# design.net
KiCad netlist of a schematic drawn in EasyEDA Pro
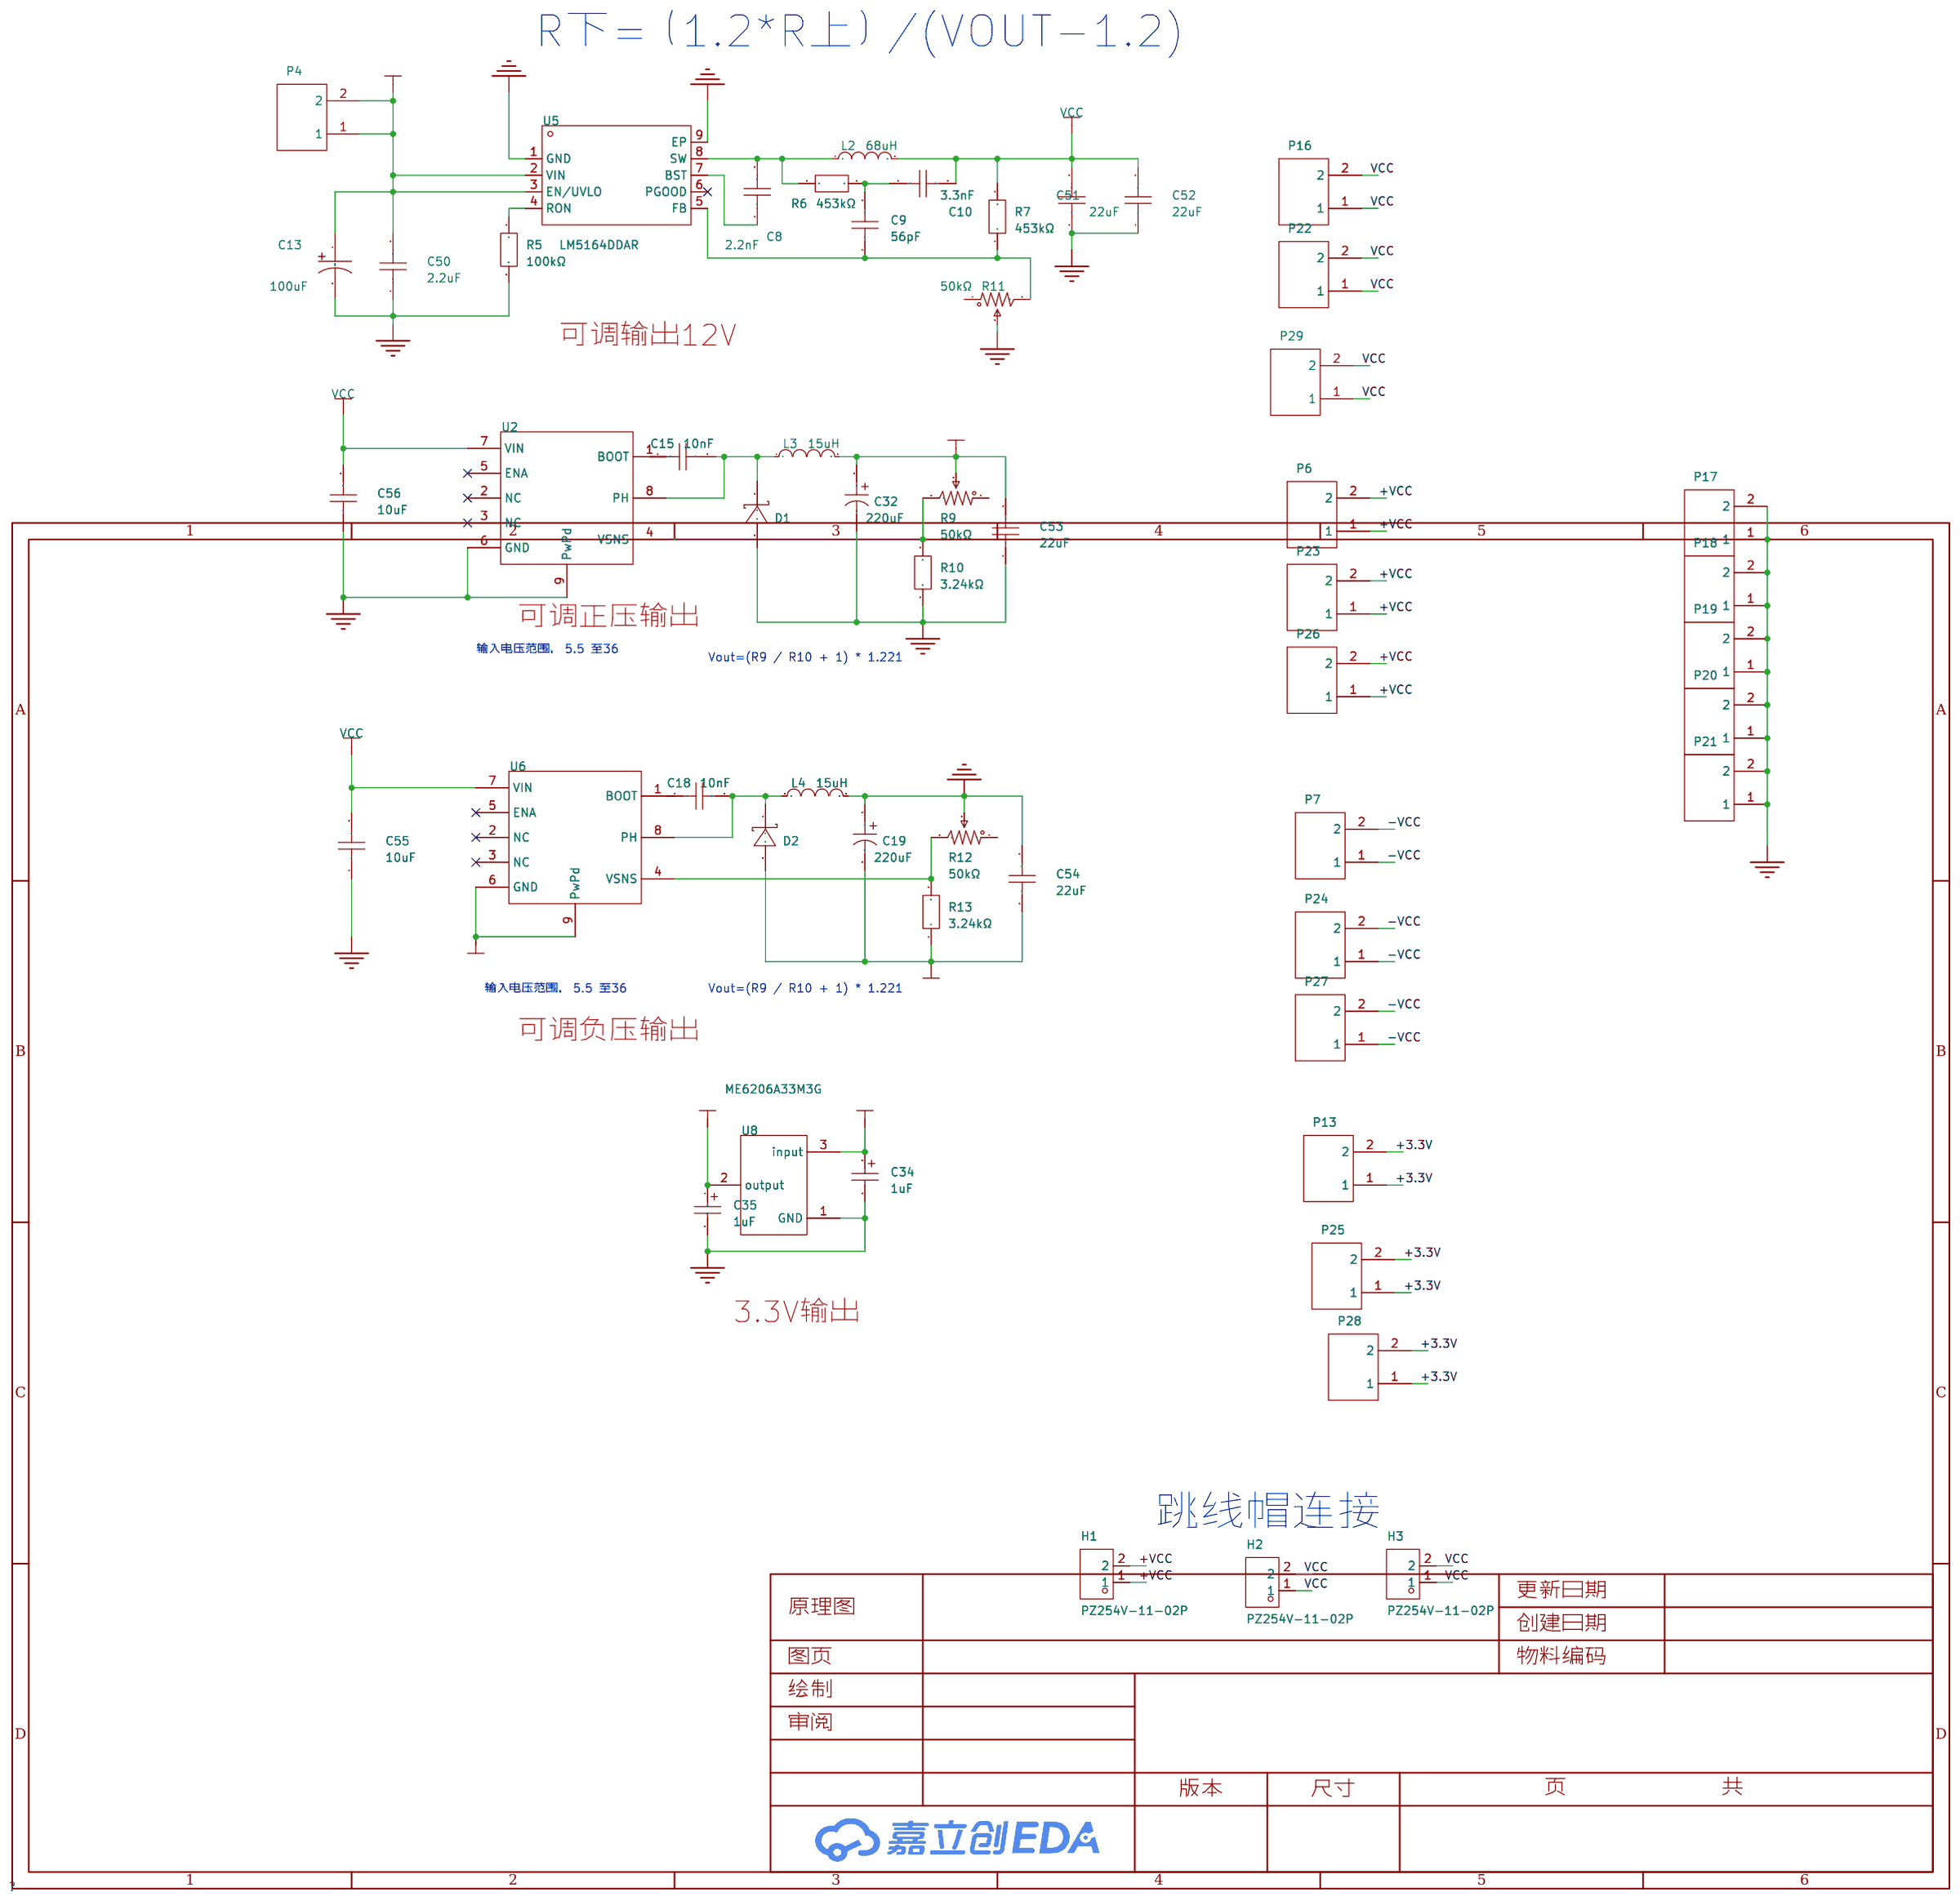
[diagram p0: schematic sheet]

(export (version "E")
  (design (tool "Eeschema 10.0.6"))
  (components
    (comp (ref "C8")
      (value "2.2nF")
      (footprint "easyedapro:C0805")
      (description "容值:2.2nF;精度:±5%;额定电压:250V;材质(温度系数):C0G;")
      (fields
        (field (name "Manufacturer Part") "C0805X222JAGACAUTO")
        (field (name "Manufacturer") "KEMET(基美)")
      )
      (libsource (lib "easyedapro") (part "C0805X222JAGACAUTO"))
    )
    (comp (ref "C9")
      (value "56pF")
      (footprint "easyedapro:C0805")
      (description "容值:56pF;精度:±5%;额定电压:250V;材质(温度系数):C0G;")
      (fields
        (field (name "Manufacturer Part") "GRM21A5C2E560JW01D")
        (field (name "Manufacturer") "muRata(村田)")
      )
      (libsource (lib "easyedapro") (part "GRM21A5C2E560JW01D"))
    )
    (comp (ref "C10")
      (value "3.3nF")
      (footprint "easyedapro:C0805")
      (description "容值:3.3nF;精度:±10%;额定电压:50V;材质(温度系数):X7R;")
      (fields
        (field (name "Manufacturer Part") "GRM216R71H332KA01D")
        (field (name "Manufacturer") "muRata(村田)")
      )
      (libsource (lib "easyedapro") (part "GRM216R71H332KA01D"))
    )
    (comp (ref "C13")
      (value "100uF")
      (footprint "easyedapro:CAP-TH_BD10.0-P5.00-D1.0-FD")
      (fields
        (field (name "Manufacturer Part") "RC100M101LO10*16TH-2A1E")
        (field (name "Manufacturer") "BERYL(绿宝石)")
      )
      (libsource (lib "easyedapro") (part "RC100M101LO10*16TH-2A1E"))
    )
    (comp (ref "C15")
      (value "10nF")
      (footprint "easyedapro:C0805")
      (description "容值:10nF;精度:±10%;额定电压:50V;材质(温度系数):X8R;")
      (fields (field (name "Manufacturer Part") "C0805C103K5HACTU") (field (name "Manufacturer") "KEMET(基美)"))
      (libsource (lib "easyedapro") (part "C0805C103K5HACTU"))
    )
    (comp (ref "C18")
      (value "10nF")
      (footprint "easyedapro:C0805")
      (description "容值:10nF;精度:±10%;额定电压:50V;材质(温度系数):X8R;")
      (fields (field (name "Manufacturer Part") "C0805C103K5HACTU") (field (name "Manufacturer") "KEMET(基美)"))
      (libsource (lib "easyedapro") (part "C0805C103K5HACTU"))
    )
    (comp (ref "C19")
      (value "220uF")
      (fields (field (name "Manufacturer Part") "ERE1VM221F12OT") (field (name "Manufacturer") "AISHI(艾华集团)"))
      (libsource (lib "easyedapro") (part "RVE100UF35V67RV0072"))
    )
    (comp (ref "C32")
      (value "220uF")
      (fields (field (name "Manufacturer Part") "ERE1VM221F12OT") (field (name "Manufacturer") "AISHI(艾华集团)"))
      (libsource (lib "easyedapro") (part "RVE100UF35V67RV0072"))
    )
    (comp (ref "C34")
      (value "1uF")
      (footprint "easyedapro:CASE-A_3216")
      (description "容值:1uF;精度:±10%;额定电压:35V;等效串联电阻:7.5Ω@100kHz;")
      (fields (field (name "Manufacturer Part") "TAJA105K035RNJ") (field (name "Manufacturer") "Kyocera AVX"))
      (libsource (lib "easyedapro") (part "TAJA105K035RNJ"))
    )
    (comp (ref "C35")
      (value "1uF")
      (footprint "easyedapro:CASE-A_3216")
      (description "容值:1uF;精度:±10%;额定电压:35V;等效串联电阻:7.5Ω@100kHz;")
      (fields (field (name "Manufacturer Part") "TAJA105K035RNJ") (field (name "Manufacturer") "Kyocera AVX"))
      (libsource (lib "easyedapro") (part "TAJA105K035RNJ"))
    )
    (comp (ref "C50")
      (value "2.2uF")
      (footprint "easyedapro:C0805")
      (description "容值:2.2uF;精度:±10%;额定电压:100V;材质(温度系数):X7R;")
      (fields
        (field (name "Manufacturer Part") "CGA0805X7R225K101MT")
        (field (name "Manufacturer") "HRE(芯声)")
      )
      (libsource (lib "easyedapro") (part "CGA0805X7R225K101MT"))
    )
    (comp (ref "C51")
      (value "22uF")
      (footprint "easyedapro:C0805")
      (description "容值:22uF;精度:±20%;额定电压:35V;材质(温度系数):X5R;")
      (fields
        (field (name "Manufacturer Part") "CGA0805X5R226M350MT")
        (field (name "Manufacturer") "HRE(芯声)")
      )
      (libsource (lib "easyedapro") (part "CGA0805X5R226M350MT"))
    )
    (comp (ref "C52")
      (value "22uF")
      (footprint "easyedapro:C0805")
      (description "容值:22uF;精度:±20%;额定电压:35V;材质(温度系数):X5R;")
      (fields
        (field (name "Manufacturer Part") "CGA0805X5R226M350MT")
        (field (name "Manufacturer") "HRE(芯声)")
      )
      (libsource (lib "easyedapro") (part "CGA0805X5R226M350MT"))
    )
    (comp (ref "C53")
      (value "22uF")
      (footprint "easyedapro:C0805")
      (description "容值:22uF;精度:±20%;额定电压:35V;材质(温度系数):X5R;")
      (fields
        (field (name "Manufacturer Part") "CGA0805X5R226M350MT")
        (field (name "Manufacturer") "HRE(芯声)")
      )
      (libsource (lib "easyedapro") (part "CGA0805X5R226M350MT"))
    )
    (comp (ref "C54")
      (value "22uF")
      (footprint "easyedapro:C0805")
      (description "容值:22uF;精度:±20%;额定电压:35V;材质(温度系数):X5R;")
      (fields
        (field (name "Manufacturer Part") "CGA0805X5R226M350MT")
        (field (name "Manufacturer") "HRE(芯声)")
      )
      (libsource (lib "easyedapro") (part "CGA0805X5R226M350MT"))
    )
    (comp (ref "C55")
      (value "10uF")
      (footprint "easyedapro:C0805")
      (description "容值:10uF;精度:±10%;额定电压:50V;材质(温度系数):X5R;")
      (fields
        (field (name "Manufacturer Part") "GRM21BR61H106KE43L")
        (field (name "Manufacturer") "muRata(村田)")
      )
      (libsource (lib "easyedapro") (part "GRM21BR61H106KE43L"))
    )
    (comp (ref "C56")
      (value "10uF")
      (footprint "easyedapro:C0805")
      (description "容值:10uF;精度:±10%;额定电压:50V;材质(温度系数):X5R;")
      (fields
        (field (name "Manufacturer Part") "GRM21BR61H106KE43L")
        (field (name "Manufacturer") "muRata(村田)")
      )
      (libsource (lib "easyedapro") (part "GRM21BR61H106KE43L"))
    )
    (comp (ref "D1")
      (value "B340A")
      (footprint "easyedapro:SMA_L4.3-W2.6-LS5.1-RD")
      (description "直流反向耐压(Vr):40V;平均整流电流(Io):3A;正向压降(Vf):550mV@3A;")
      (fields (field (name "Manufacturer") "MDD"))
      (libsource (lib "easyedapro") (part "B340A"))
    )
    (comp (ref "D2")
      (value "B340A")
      (footprint "easyedapro:SMA_L4.3-W2.6-LS5.1-RD")
      (description "直流反向耐压(Vr):40V;平均整流电流(Io):3A;正向压降(Vf):550mV@3A;")
      (fields (field (name "Manufacturer") "MDD"))
      (libsource (lib "easyedapro") (part "B340A"))
    )
    (comp (ref "H1")
      (value "PZ254V-11-02P")
      (footprint "easyedapro:HDR-TH_2P-P2.54-V-M")
      (fields (field (name "Manufacturer") "XFCN(兴飞)"))
      (libsource (lib "easyedapro") (part "PZ254V-11-02P"))
    )
    (comp (ref "H2")
      (value "PZ254V-11-02P")
      (footprint "easyedapro:HDR-TH_2P-P2.54-V-M")
      (fields (field (name "Manufacturer") "XFCN(兴飞)"))
      (libsource (lib "easyedapro") (part "PZ254V-11-02P"))
    )
    (comp (ref "H3")
      (value "PZ254V-11-02P")
      (footprint "easyedapro:HDR-TH_2P-P2.54-V-M")
      (fields (field (name "Manufacturer") "XFCN(兴飞)"))
      (libsource (lib "easyedapro") (part "PZ254V-11-02P"))
    )
    (comp (ref "L2")
      (value "68uH")
      (footprint "easyedapro:IND-SMD_L13.5-W12.8_APH1265T")
      (description "电感值:68uH;精度:±20%;额定电流:4.1A;饱和电流(Isat):4.3A;类型:一体成型电感;")
      (fields (field (name "Manufacturer Part") "APH1265T680M") (field (name "Manufacturer") "APV(爱普微)"))
      (libsource (lib "easyedapro") (part "APH1265T680M"))
    )
    (comp (ref "L3")
      (value "15uH")
      (footprint "easyedapro:IND-SMD_L7.3-W6.8")
      (description "精度:±20%;额定电流:3A;电感值:15uH;直流电阻(DCR):113mΩ;")
      (fields
        (field (name "Manufacturer Part") "MWSA0603S-150MT")
        (field (name "Manufacturer") "Sunlord(顺络)")
      )
      (libsource (lib "easyedapro") (part "MWSA0603S-150MT"))
    )
    (comp (ref "L4")
      (value "15uH")
      (footprint "easyedapro:IND-SMD_L7.3-W6.8")
      (description "精度:±20%;额定电流:3A;电感值:15uH;直流电阻(DCR):113mΩ;")
      (fields
        (field (name "Manufacturer Part") "MWSA0603S-150MT")
        (field (name "Manufacturer") "Sunlord(顺络)")
      )
      (libsource (lib "easyedapro") (part "MWSA0603S-150MT"))
    )
    (comp (ref "P4")
      (value "WJ128V-5.0-2P")
      (footprint "easyedapro:CONN-TH_2P-P5.00_WJ128V-5.0-2P")
      (fields (field (name "Manufacturer") "KANGNEX(康奈克斯电气)"))
      (libsource (lib "easyedapro") (part "WJ128V-5.0-2P"))
    )
    (comp (ref "P6")
      (value "WJ128V-5.0-2P")
      (footprint "easyedapro:CONN-TH_2P-P5.00_WJ128V-5.0-2P")
      (fields (field (name "Manufacturer") "KANGNEX(康奈克斯电气)"))
      (libsource (lib "easyedapro") (part "WJ128V-5.0-2P"))
    )
    (comp (ref "P7")
      (value "WJ128V-5.0-2P")
      (footprint "easyedapro:CONN-TH_2P-P5.00_WJ128V-5.0-2P")
      (fields (field (name "Manufacturer") "KANGNEX(康奈克斯电气)"))
      (libsource (lib "easyedapro") (part "WJ128V-5.0-2P"))
    )
    (comp (ref "P13")
      (value "WJ128V-5.0-2P")
      (footprint "easyedapro:CONN-TH_2P-P5.00_WJ128V-5.0-2P")
      (fields (field (name "Manufacturer") "KANGNEX(康奈克斯电气)"))
      (libsource (lib "easyedapro") (part "WJ128V-5.0-2P"))
    )
    (comp (ref "P16")
      (value "WJ128V-5.0-2P")
      (footprint "easyedapro:CONN-TH_2P-P5.00_WJ128V-5.0-2P")
      (fields (field (name "Manufacturer") "KANGNEX(康奈克斯电气)"))
      (libsource (lib "easyedapro") (part "WJ128V-5.0-2P"))
    )
    (comp (ref "P17")
      (value "WJ128V-5.0-2P")
      (footprint "easyedapro:CONN-TH_2P-P5.00_WJ128V-5.0-2P")
      (fields (field (name "Manufacturer") "KANGNEX(康奈克斯电气)"))
      (libsource (lib "easyedapro") (part "WJ128V-5.0-2P"))
    )
    (comp (ref "P18")
      (value "WJ128V-5.0-2P")
      (footprint "easyedapro:CONN-TH_2P-P5.00_WJ128V-5.0-2P")
      (fields (field (name "Manufacturer") "KANGNEX(康奈克斯电气)"))
      (libsource (lib "easyedapro") (part "WJ128V-5.0-2P"))
    )
    (comp (ref "P19")
      (value "WJ128V-5.0-2P")
      (footprint "easyedapro:CONN-TH_2P-P5.00_WJ128V-5.0-2P")
      (fields (field (name "Manufacturer") "KANGNEX(康奈克斯电气)"))
      (libsource (lib "easyedapro") (part "WJ128V-5.0-2P"))
    )
    (comp (ref "P20")
      (value "WJ128V-5.0-2P")
      (footprint "easyedapro:CONN-TH_2P-P5.00_WJ128V-5.0-2P")
      (fields (field (name "Manufacturer") "KANGNEX(康奈克斯电气)"))
      (libsource (lib "easyedapro") (part "WJ128V-5.0-2P"))
    )
    (comp (ref "P21")
      (value "WJ128V-5.0-2P")
      (footprint "easyedapro:CONN-TH_2P-P5.00_WJ128V-5.0-2P")
      (fields (field (name "Manufacturer") "KANGNEX(康奈克斯电气)"))
      (libsource (lib "easyedapro") (part "WJ128V-5.0-2P"))
    )
    (comp (ref "P22")
      (value "WJ128V-5.0-2P")
      (footprint "easyedapro:CONN-TH_2P-P5.00_WJ128V-5.0-2P")
      (fields (field (name "Manufacturer") "KANGNEX(康奈克斯电气)"))
      (libsource (lib "easyedapro") (part "WJ128V-5.0-2P"))
    )
    (comp (ref "P23")
      (value "WJ128V-5.0-2P")
      (footprint "easyedapro:CONN-TH_2P-P5.00_WJ128V-5.0-2P")
      (fields (field (name "Manufacturer") "KANGNEX(康奈克斯电气)"))
      (libsource (lib "easyedapro") (part "WJ128V-5.0-2P"))
    )
    (comp (ref "P24")
      (value "WJ128V-5.0-2P")
      (footprint "easyedapro:CONN-TH_2P-P5.00_WJ128V-5.0-2P")
      (fields (field (name "Manufacturer") "KANGNEX(康奈克斯电气)"))
      (libsource (lib "easyedapro") (part "WJ128V-5.0-2P"))
    )
    (comp (ref "P25")
      (value "WJ128V-5.0-2P")
      (footprint "easyedapro:CONN-TH_2P-P5.00_WJ128V-5.0-2P")
      (fields (field (name "Manufacturer") "KANGNEX(康奈克斯电气)"))
      (libsource (lib "easyedapro") (part "WJ128V-5.0-2P"))
    )
    (comp (ref "P26")
      (value "WJ128V-5.0-2P")
      (footprint "easyedapro:CONN-TH_2P-P5.00_WJ128V-5.0-2P")
      (fields (field (name "Manufacturer") "KANGNEX(康奈克斯电气)"))
      (libsource (lib "easyedapro") (part "WJ128V-5.0-2P"))
    )
    (comp (ref "P27")
      (value "WJ128V-5.0-2P")
      (footprint "easyedapro:CONN-TH_2P-P5.00_WJ128V-5.0-2P")
      (fields (field (name "Manufacturer") "KANGNEX(康奈克斯电气)"))
      (libsource (lib "easyedapro") (part "WJ128V-5.0-2P"))
    )
    (comp (ref "P28")
      (value "WJ128V-5.0-2P")
      (footprint "easyedapro:CONN-TH_2P-P5.00_WJ128V-5.0-2P")
      (fields (field (name "Manufacturer") "KANGNEX(康奈克斯电气)"))
      (libsource (lib "easyedapro") (part "WJ128V-5.0-2P"))
    )
    (comp (ref "P29")
      (value "WJ128V-5.0-2P")
      (footprint "easyedapro:CONN-TH_2P-P5.00_WJ128V-5.0-2P")
      (fields (field (name "Manufacturer") "KANGNEX(康奈克斯电气)"))
      (libsource (lib "easyedapro") (part "WJ128V-5.0-2P"))
    )
    (comp (ref "R5")
      (value "100kΩ")
      (footprint "easyedapro:R0805")
      (description "电阻类型:薄膜电阻;阻值:100kΩ;精度:±0.01%;温度系数:±5ppm/°C;")
      (fields
        (field (name "Manufacturer Part") "TP0805T100KP0505Z")
        (field (name "Manufacturer") "EVER OHMS(天二科技)")
      )
      (libsource (lib "easyedapro") (part "TP0805T100KP0505Z"))
    )
    (comp (ref "R6")
      (value "453kΩ")
      (footprint "easyedapro:R0805")
      (description "电阻类型:薄膜电阻;阻值:100kΩ;精度:±0.01%;温度系数:±5ppm/°C;")
      (fields
        (field (name "Manufacturer Part") "TP0805T100KP0505Z")
        (field (name "Manufacturer") "EVER OHMS(天二科技)")
      )
      (libsource (lib "easyedapro") (part "TP0805T100KP0505Z"))
    )
    (comp (ref "R7")
      (value "453kΩ")
      (footprint "easyedapro:R0805")
      (description "电阻类型:薄膜电阻;阻值:453kΩ;精度:±0.5%;功率:100mW;最大工作电压:100V;温度系数:±25ppm/°C;")
      (fields (field (name "Manufacturer Part") "RR1220P-4533-D-M") (field (name "Manufacturer") "SUSUMU"))
      (libsource (lib "easyedapro") (part "RR1220P-4533-D-M"))
    )
    (comp (ref "R9")
      (value "50kΩ")
      (fields (field (name "Manufacturer Part") "3296W-1-503") (field (name "Manufacturer") "BOCHEN(博晨)"))
      (libsource (lib "easyedapro") (part "3296W-1-103"))
    )
    (comp (ref "R10")
      (value "3.24kΩ")
      (footprint "easyedapro:R0805")
      (description "阻值:3.24kΩ;精度:±1%;功率:125mW;")
      (fields (field (name "Manufacturer Part") "RCA053K24FLF") (field (name "Manufacturer") "HKR(香港电阻)"))
      (libsource (lib "easyedapro") (part "RCA053K24FLF"))
    )
    (comp (ref "R11")
      (value "50kΩ")
      (fields (field (name "Manufacturer Part") "3296W-1-503") (field (name "Manufacturer") "BOCHEN(博晨)"))
      (libsource (lib "easyedapro") (part "3296W-1-103"))
    )
    (comp (ref "R12")
      (value "50kΩ")
      (fields (field (name "Manufacturer Part") "3296W-1-503") (field (name "Manufacturer") "BOCHEN(博晨)"))
      (libsource (lib "easyedapro") (part "3296W-1-103"))
    )
    (comp (ref "R13")
      (value "3.24kΩ")
      (footprint "easyedapro:R0805")
      (description "阻值:3.24kΩ;精度:±1%;功率:125mW;")
      (fields (field (name "Manufacturer Part") "RCA053K24FLF") (field (name "Manufacturer") "HKR(香港电阻)"))
      (libsource (lib "easyedapro") (part "RCA053K24FLF"))
    )
    (comp (ref "U2")
      (value "TPS5430DDAR")
      (footprint "easyedapro:ESOP-8_L4.9-W3.9-P1.27-LS6.0-TL-EP")
      (description "功能类型:降压型;同步整流:-;输出通道数:-;拓扑结构:-;输入电压:-;输出电流(最大值):-;开关频率:-;")
      (fields (field (name "Manufacturer") "TI(德州仪器)"))
      (libsource (lib "easyedapro") (part "TPS5430DDAR"))
    )
    (comp (ref "U5")
      (value "LM5164DDAR")
      (footprint "easyedapro:SO-8_L4.9-W3.9-P1.27-LS6.0-BL-EP")
      (description "功能类型:降压型;输出类型:可调;输入电压:6V~100V;输出电压:1.2V~100V;输出电流(最大值):1A;")
      (fields (field (name "Manufacturer") "TI(德州仪器)"))
      (libsource (lib "easyedapro") (part "LM5164DDAR"))
    )
    (comp (ref "U6")
      (value "TPS5430DDAR")
      (footprint "easyedapro:ESOP-8_L4.9-W3.9-P1.27-LS6.0-TL-EP")
      (description "功能类型:降压型;同步整流:-;输出通道数:-;拓扑结构:-;输入电压:-;输出电流(最大值):-;开关频率:-;")
      (fields (field (name "Manufacturer") "TI(德州仪器)"))
      (libsource (lib "easyedapro") (part "TPS5430DDAR"))
    )
    (comp (ref "U8")
      (value "ME6206A33M3G")
      (footprint "easyedapro:SOT-23-3_L2.9-W1.6-P1.90-LS2.8-BR")
      (description "输出类型:固定;输出极性:正;最大输入电压:6V;输出电压:3.3V;输出电流:300mA;电源纹波抑制比(PSRR):50dB@(1kHz);")
      (fields (field (name "Manufacturer") "MICRONE(南京微盟)"))
      (libsource (lib "easyedapro") (part "ME6206A33M3G"))
    )
  )
  (nets
    (net (code "1") (name "+3.3V") (class "Default")
      (node (ref "C35") (pin "1") (pinfunction "1_1") (pintype "input"))
      (node (ref "P13") (pin "1") (pinfunction "1_1") (pintype "unspecified"))
      (node (ref "P13") (pin "2") (pinfunction "2_2") (pintype "unspecified"))
      (node (ref "P25") (pin "1") (pinfunction "1_1") (pintype "unspecified"))
      (node (ref "P25") (pin "2") (pinfunction "2_2") (pintype "unspecified"))
      (node (ref "P28") (pin "1") (pinfunction "1_1") (pintype "unspecified"))
      (node (ref "P28") (pin "2") (pinfunction "2_2") (pintype "unspecified"))
      (node (ref "U8") (pin "2") (pinfunction "output_2") (pintype "input"))
    )
    (net (code "2") (name "+VCC") (class "Default")
      (node (ref "C32") (pin "1") (pinfunction "1_1") (pintype "input"))
      (node (ref "C34") (pin "1") (pinfunction "1_1") (pintype "input"))
      (node (ref "C53") (pin "2") (pinfunction "2_2") (pintype "unspecified"))
      (node (ref "H1") (pin "1") (pinfunction "1_1") (pintype "unspecified"))
      (node (ref "H1") (pin "2") (pinfunction "2_2") (pintype "unspecified"))
      (node (ref "L3") (pin "2") (pinfunction "2_2") (pintype "input"))
      (node (ref "P23") (pin "1") (pinfunction "1_1") (pintype "unspecified"))
      (node (ref "P23") (pin "2") (pinfunction "2_2") (pintype "unspecified"))
      (node (ref "P26") (pin "1") (pinfunction "1_1") (pintype "unspecified"))
      (node (ref "P26") (pin "2") (pinfunction "2_2") (pintype "unspecified"))
      (node (ref "P6") (pin "1") (pinfunction "1_1") (pintype "unspecified"))
      (node (ref "P6") (pin "2") (pinfunction "2_2") (pintype "unspecified"))
      (node (ref "R9") (pin "2") (pinfunction "2_2") (pintype "input"))
      (node (ref "U8") (pin "3") (pinfunction "input_3") (pintype "input"))
    )
    (net (code "3") (name "-VCC") (class "Default")
      (node (ref "C19") (pin "2") (pinfunction "2_2") (pintype "input"))
      (node (ref "C54") (pin "1") (pinfunction "1_1") (pintype "unspecified"))
      (node (ref "D2") (pin "2") (pinfunction "A_2") (pintype "input"))
      (node (ref "P24") (pin "1") (pinfunction "1_1") (pintype "unspecified"))
      (node (ref "P24") (pin "2") (pinfunction "2_2") (pintype "unspecified"))
      (node (ref "P27") (pin "1") (pinfunction "1_1") (pintype "unspecified"))
      (node (ref "P27") (pin "2") (pinfunction "2_2") (pintype "unspecified"))
      (node (ref "P7") (pin "1") (pinfunction "1_1") (pintype "unspecified"))
      (node (ref "P7") (pin "2") (pinfunction "2_2") (pintype "unspecified"))
      (node (ref "R13") (pin "1") (pinfunction "1_1") (pintype "unspecified"))
      (node (ref "U6") (pin "6") (pinfunction "GND_6") (pintype "input"))
      (node (ref "U6") (pin "9") (pinfunction "PwPd_9") (pintype "input"))
    )
    (net (code "4") (name "GND") (class "Default")
      (node (ref "C13") (pin "2") (pinfunction "2_2") (pintype "input"))
      (node (ref "C19") (pin "1") (pinfunction "1_1") (pintype "input"))
      (node (ref "C32") (pin "2") (pinfunction "2_2") (pintype "input"))
      (node (ref "C34") (pin "2") (pinfunction "2_2") (pintype "input"))
      (node (ref "C35") (pin "2") (pinfunction "2_2") (pintype "input"))
      (node (ref "C50") (pin "1") (pinfunction "1_1") (pintype "unspecified"))
      (node (ref "C51") (pin "1") (pinfunction "1_1") (pintype "unspecified"))
      (node (ref "C52") (pin "1") (pinfunction "1_1") (pintype "unspecified"))
      (node (ref "C53") (pin "1") (pinfunction "1_1") (pintype "unspecified"))
      (node (ref "C54") (pin "2") (pinfunction "2_2") (pintype "unspecified"))
      (node (ref "C55") (pin "1") (pinfunction "1_1") (pintype "unspecified"))
      (node (ref "C56") (pin "1") (pinfunction "1_1") (pintype "unspecified"))
      (node (ref "D1") (pin "2") (pinfunction "A_2") (pintype "input"))
      (node (ref "L4") (pin "2") (pinfunction "2_2") (pintype "input"))
      (node (ref "P17") (pin "1") (pinfunction "1_1") (pintype "unspecified"))
      (node (ref "P17") (pin "2") (pinfunction "2_2") (pintype "unspecified"))
      (node (ref "P18") (pin "1") (pinfunction "1_1") (pintype "unspecified"))
      (node (ref "P18") (pin "2") (pinfunction "2_2") (pintype "unspecified"))
      (node (ref "P19") (pin "1") (pinfunction "1_1") (pintype "unspecified"))
      (node (ref "P19") (pin "2") (pinfunction "2_2") (pintype "unspecified"))
      (node (ref "P20") (pin "1") (pinfunction "1_1") (pintype "unspecified"))
      (node (ref "P20") (pin "2") (pinfunction "2_2") (pintype "unspecified"))
      (node (ref "P21") (pin "1") (pinfunction "1_1") (pintype "unspecified"))
      (node (ref "P21") (pin "2") (pinfunction "2_2") (pintype "unspecified"))
      (node (ref "R10") (pin "1") (pinfunction "1_1") (pintype "unspecified"))
      (node (ref "R11") (pin "2") (pinfunction "2_2") (pintype "input"))
      (node (ref "R12") (pin "2") (pinfunction "2_2") (pintype "input"))
      (node (ref "R5") (pin "2") (pinfunction "2_2") (pintype "unspecified"))
      (node (ref "U2") (pin "6") (pinfunction "GND_6") (pintype "input"))
      (node (ref "U2") (pin "9") (pinfunction "PwPd_9") (pintype "input"))
      (node (ref "U5") (pin "1") (pinfunction "GND_1") (pintype "input"))
      (node (ref "U5") (pin "9") (pinfunction "EP_9") (pintype "input"))
      (node (ref "U8") (pin "1") (pinfunction "GND_1") (pintype "input"))
    )
    (net (code "5") (name "Net-(C10-Pad1)") (class "Default")
      (node (ref "C10") (pin "1") (pinfunction "1_1") (pintype "unspecified"))
      (node (ref "C9") (pin "2") (pinfunction "2_2") (pintype "unspecified"))
      (node (ref "R6") (pin "1") (pinfunction "1_1") (pintype "unspecified"))
    )
    (net (code "6") (name "Net-(D1-K)") (class "Default")
      (node (ref "C15") (pin "2") (pinfunction "2_2") (pintype "unspecified"))
      (node (ref "D1") (pin "1") (pinfunction "K_1") (pintype "input"))
      (node (ref "L3") (pin "1") (pinfunction "1_1") (pintype "input"))
      (node (ref "U2") (pin "8") (pinfunction "PH_8") (pintype "input"))
    )
    (net (code "7") (name "Net-(D2-K)") (class "Default")
      (node (ref "C18") (pin "2") (pinfunction "2_2") (pintype "unspecified"))
      (node (ref "D2") (pin "1") (pinfunction "K_1") (pintype "input"))
      (node (ref "L4") (pin "1") (pinfunction "1_1") (pintype "input"))
      (node (ref "U6") (pin "8") (pinfunction "PH_8") (pintype "input"))
    )
    (net (code "8") (name "Net-(U2-BOOT)") (class "Default")
      (node (ref "C15") (pin "1") (pinfunction "1_1") (pintype "unspecified"))
      (node (ref "U2") (pin "1") (pinfunction "BOOT_1") (pintype "input"))
    )
    (net (code "9") (name "Net-(U2-VSNS)") (class "Default")
      (node (ref "R10") (pin "2") (pinfunction "2_2") (pintype "unspecified"))
      (node (ref "R9") (pin "3") (pinfunction "3_3") (pintype "input"))
      (node (ref "U2") (pin "4") (pinfunction "VSNS_4") (pintype "input"))
    )
    (net (code "10") (name "Net-(U5-BST)") (class "Default")
      (node (ref "C8") (pin "1") (pinfunction "1_1") (pintype "unspecified"))
      (node (ref "U5") (pin "7") (pinfunction "BST_7") (pintype "input"))
    )
    (net (code "11") (name "Net-(U5-FB)") (class "Default")
      (node (ref "C9") (pin "1") (pinfunction "1_1") (pintype "unspecified"))
      (node (ref "R11") (pin "3") (pinfunction "3_3") (pintype "input"))
      (node (ref "R7") (pin "1") (pinfunction "1_1") (pintype "unspecified"))
      (node (ref "U5") (pin "5") (pinfunction "FB_5") (pintype "input"))
    )
    (net (code "12") (name "Net-(U5-RON)") (class "Default")
      (node (ref "R5") (pin "1") (pinfunction "1_1") (pintype "unspecified"))
      (node (ref "U5") (pin "4") (pinfunction "RON_4") (pintype "input"))
    )
    (net (code "13") (name "Net-(U5-SW)") (class "Default")
      (node (ref "C8") (pin "2") (pinfunction "2_2") (pintype "unspecified"))
      (node (ref "L2") (pin "1") (pinfunction "1_1") (pintype "unspecified"))
      (node (ref "R6") (pin "2") (pinfunction "2_2") (pintype "unspecified"))
      (node (ref "U5") (pin "8") (pinfunction "SW_8") (pintype "input"))
    )
    (net (code "14") (name "Net-(U6-BOOT)") (class "Default")
      (node (ref "C18") (pin "1") (pinfunction "1_1") (pintype "unspecified"))
      (node (ref "U6") (pin "1") (pinfunction "BOOT_1") (pintype "input"))
    )
    (net (code "15") (name "Net-(U6-VSNS)") (class "Default")
      (node (ref "R12") (pin "3") (pinfunction "3_3") (pintype "input"))
      (node (ref "R13") (pin "2") (pinfunction "2_2") (pintype "unspecified"))
      (node (ref "U6") (pin "4") (pinfunction "VSNS_4") (pintype "input"))
    )
    (net (code "16") (name "VCC") (class "Default")
      (node (ref "C10") (pin "2") (pinfunction "2_2") (pintype "unspecified"))
      (node (ref "C51") (pin "2") (pinfunction "2_2") (pintype "unspecified"))
      (node (ref "C52") (pin "2") (pinfunction "2_2") (pintype "unspecified"))
      (node (ref "C55") (pin "2") (pinfunction "2_2") (pintype "unspecified"))
      (node (ref "C56") (pin "2") (pinfunction "2_2") (pintype "unspecified"))
      (node (ref "H2") (pin "1") (pinfunction "1_1") (pintype "unspecified"))
      (node (ref "H2") (pin "2") (pinfunction "2_2") (pintype "unspecified"))
      (node (ref "H3") (pin "1") (pinfunction "1_1") (pintype "unspecified"))
      (node (ref "H3") (pin "2") (pinfunction "2_2") (pintype "unspecified"))
      (node (ref "L2") (pin "2") (pinfunction "2_2") (pintype "unspecified"))
      (node (ref "P16") (pin "1") (pinfunction "1_1") (pintype "unspecified"))
      (node (ref "P16") (pin "2") (pinfunction "2_2") (pintype "unspecified"))
      (node (ref "P22") (pin "1") (pinfunction "1_1") (pintype "unspecified"))
      (node (ref "P22") (pin "2") (pinfunction "2_2") (pintype "unspecified"))
      (node (ref "P29") (pin "1") (pinfunction "1_1") (pintype "unspecified"))
      (node (ref "P29") (pin "2") (pinfunction "2_2") (pintype "unspecified"))
      (node (ref "R7") (pin "2") (pinfunction "2_2") (pintype "unspecified"))
      (node (ref "U2") (pin "7") (pinfunction "VIN_7") (pintype "input"))
      (node (ref "U6") (pin "7") (pinfunction "VIN_7") (pintype "input"))
    )
    (net (code "17") (name "VIN") (class "Default")
      (node (ref "C13") (pin "1") (pinfunction "1_1") (pintype "input"))
      (node (ref "C50") (pin "2") (pinfunction "2_2") (pintype "unspecified"))
      (node (ref "P4") (pin "1") (pinfunction "1_1") (pintype "unspecified"))
      (node (ref "P4") (pin "2") (pinfunction "2_2") (pintype "unspecified"))
      (node (ref "U5") (pin "2") (pinfunction "VIN_2") (pintype "input"))
      (node (ref "U5") (pin "3") (pinfunction "EN/UVLO_3") (pintype "input"))
    )
    (net (code "18") (name "unconnected-(R9-Pad1)") (class "Default")
      (node (ref "R9") (pin "1") (pinfunction "1_1") (pintype "input"))
    )
    (net (code "19") (name "unconnected-(R11-Pad1)") (class "Default")
      (node (ref "R11") (pin "1") (pinfunction "1_1") (pintype "input"))
    )
    (net (code "20") (name "unconnected-(R12-Pad1)") (class "Default")
      (node (ref "R12") (pin "1") (pinfunction "1_1") (pintype "input"))
    )
    (net (code "21") (name "unconnected-(U2-ENA-Pad5)") (class "Default")
      (node (ref "U2") (pin "5") (pinfunction "ENA_5") (pintype "input+no_connect"))
    )
    (net (code "22") (name "unconnected-(U2-NC-Pad2)") (class "Default")
      (node (ref "U2") (pin "2") (pinfunction "NC_2") (pintype "input+no_connect"))
    )
    (net (code "23") (name "unconnected-(U2-NC-Pad3)") (class "Default")
      (node (ref "U2") (pin "3") (pinfunction "NC_3") (pintype "input+no_connect"))
    )
    (net (code "24") (name "unconnected-(U5-PGOOD-Pad6)") (class "Default")
      (node (ref "U5") (pin "6") (pinfunction "PGOOD_6") (pintype "input+no_connect"))
    )
    (net (code "25") (name "unconnected-(U6-ENA-Pad5)") (class "Default")
      (node (ref "U6") (pin "5") (pinfunction "ENA_5") (pintype "input+no_connect"))
    )
    (net (code "26") (name "unconnected-(U6-NC-Pad2)") (class "Default")
      (node (ref "U6") (pin "2") (pinfunction "NC_2") (pintype "input+no_connect"))
    )
    (net (code "27") (name "unconnected-(U6-NC-Pad3)") (class "Default")
      (node (ref "U6") (pin "3") (pinfunction "NC_3") (pintype "input+no_connect"))
    )
  )
)
